# EIS_CO2_Power.net
KiCad netlist of a schematic drawn in Altium Designer
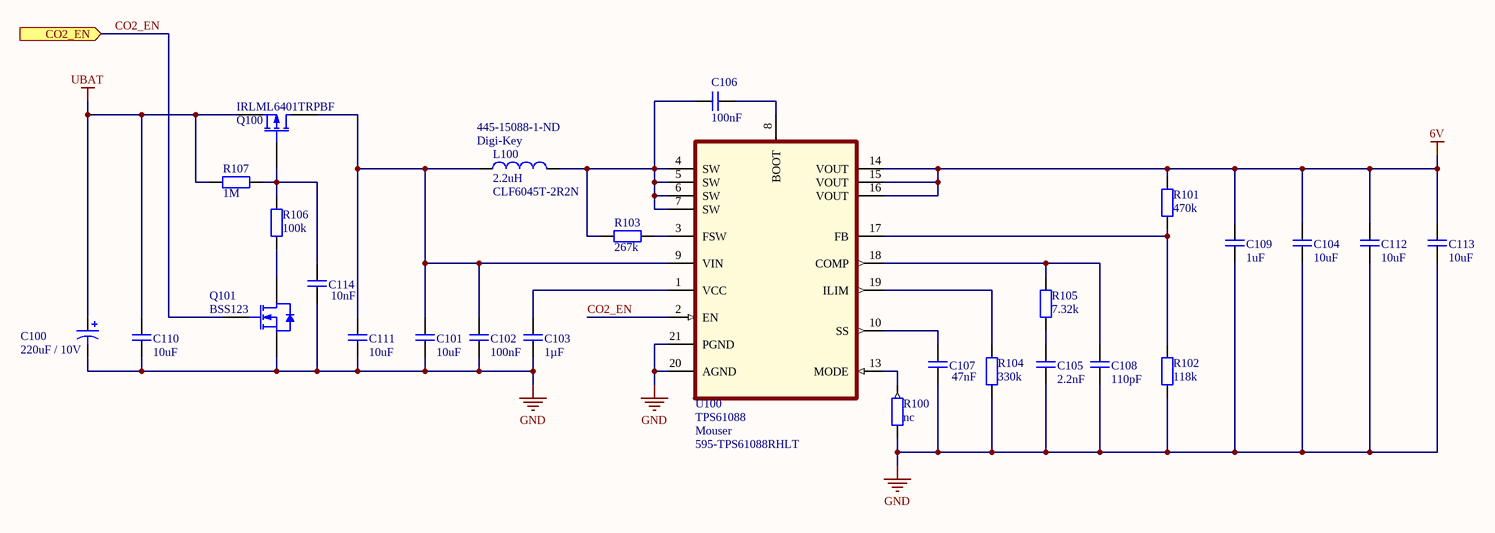
[diagram p0: EIS_CO2_Power.SchDoc]

(export (version "E")
  (design (tool "Eeschema 10.0.6"))
  (components
    (comp (ref "C100")
      (value "220uF / 10V")
      (footprint "D")
      (description "Polarized Capacitor (Surface Mount)")
      (fields (field (name "PUBLISHER") "Altium Limited"))
      (libsource (lib "Miscellaneous Devices") (part "Cap Pol3"))
    )
    (comp (ref "C101")
      (value "10uF")
      (footprint "CAPC3216N")
      (libsource (lib "My_Schlib_6_18") (part "Kondensator SMD Keramik"))
    )
    (comp (ref "C102")
      (value "100nF")
      (footprint "CAPC1608N")
      (libsource (lib "My_Schlib_6_18") (part "Kondensator SMD Keramik"))
    )
    (comp (ref "C103")
      (value "1µF")
      (footprint "CAPC1608N")
      (libsource (lib "My_Schlib_6_18") (part "Kondensator SMD Keramik"))
    )
    (comp (ref "C104")
      (value "10uF")
      (footprint "CAPC3216N")
      (libsource (lib "My_Schlib_6_18") (part "Kondensator SMD Keramik"))
    )
    (comp (ref "C105")
      (value "2.2nF")
      (footprint "CAPC1608N")
      (libsource (lib "My_Schlib_6_18") (part "Kondensator SMD Keramik"))
    )
    (comp (ref "C106")
      (value "100nF")
      (footprint "CAPC1608N")
      (libsource (lib "My_Schlib_6_18") (part "Kondensator SMD Keramik"))
    )
    (comp (ref "C107")
      (value "47nF")
      (footprint "CAPC1608N")
      (libsource (lib "My_Schlib_6_18") (part "Kondensator SMD Keramik"))
    )
    (comp (ref "C108")
      (value "110pF")
      (footprint "CAPC1608N")
      (libsource (lib "My_Schlib_6_18") (part "Kondensator SMD Keramik"))
    )
    (comp (ref "C109")
      (value "1uF")
      (footprint "CAPC3216N")
      (libsource (lib "My_Schlib_6_18") (part "Kondensator SMD Keramik"))
    )
    (comp (ref "C110")
      (value "10uF")
      (footprint "CAPC3216N")
      (libsource (lib "My_Schlib_6_18") (part "Kondensator SMD Keramik"))
    )
    (comp (ref "C111")
      (value "10uF")
      (footprint "CAPC3216N")
      (libsource (lib "My_Schlib_6_18") (part "Kondensator SMD Keramik"))
    )
    (comp (ref "C112")
      (value "10uF")
      (footprint "CAPC3216N")
      (libsource (lib "My_Schlib_6_18") (part "Kondensator SMD Keramik"))
    )
    (comp (ref "C113")
      (value "10uF")
      (footprint "CAPC3216N")
      (libsource (lib "My_Schlib_6_18") (part "Kondensator SMD Keramik"))
    )
    (comp (ref "C114")
      (value "10nF")
      (footprint "CAPC1608N")
      (libsource (lib "My_Schlib_6_18") (part "Kondensator SMD Keramik"))
    )
    (comp (ref "L100")
      (value "2.2uH")
      (footprint "CLF6045")
      (description "Inductor")
      (fields
        (field (name "SUPPLIER PART NUMBER 1") "CLF6045T-2R2N")
        (field (name "SUPPLIER 2") "Digi-Key")
        (field (name "SUPPLIER PART NUMBER 2") "445-15088-1-ND")
        (field (name "Comment") "CLF6045T-2R2N")
        (field (name "PUBLISHER") "Altium Limited")
      )
      (libsource (lib "MetaSensClampOn_BT") (part "Inductor"))
    )
    (comp (ref "Q100")
      (value "IRLML6401TRPBF")
      (footprint "SOT23_N")
      (description "P-Channel MOSFET")
      (fields (field (name "PUBLISHER") "Altium Limited"))
      (libsource (lib "Eis_Lib") (part "IRLML6401TRPBF"))
    )
    (comp (ref "Q101")
      (value "BSS123")
      (footprint "SOT23_N - BSS123")
      (description "N-channel Enhancement Mode Vertical D-MOSFET")
      (fields (field (name "PUBLISHER") "Altium Limited"))
      (libsource (lib "Philips Discrete MOSFET - Low Power") (part "BSS123"))
    )
    (comp (ref "R100")
      (value "nc")
      (footprint "RESC1608N")
      (description "RESC1608 (R0603)")
      (fields (field (name "PUBLISHER") "HSG Jürgen Merz"))
      (libsource (lib "MetaSensClampOn_BT") (part "RESC1608 (R0603)"))
    )
    (comp (ref "R101")
      (value "470k")
      (footprint "RESC1608N")
      (description "RESC1608 (R0603)")
      (fields (field (name "PUBLISHER") "HSG Jürgen Merz"))
      (libsource (lib "MetaSensClampOn_BT") (part "RESC1608 (R0603)"))
    )
    (comp (ref "R102")
      (value "118k")
      (footprint "RESC1608N")
      (description "RESC1608 (R0603)")
      (fields (field (name "PUBLISHER") "HSG Jürgen Merz"))
      (libsource (lib "MetaSensClampOn_BT") (part "RESC1608 (R0603)"))
    )
    (comp (ref "R103")
      (value "267k")
      (footprint "RESC1608N")
      (description "RESC1608 (R0603)")
      (fields (field (name "PUBLISHER") "HSG Jürgen Merz"))
      (libsource (lib "") (part "RESC1608 (R0603)_2"))
    )
    (comp (ref "R104")
      (value "330k")
      (footprint "RESC1608N")
      (description "RESC1608 (R0603)")
      (fields (field (name "PUBLISHER") "HSG Jürgen Merz"))
      (libsource (lib "MetaSensClampOn_BT") (part "RESC1608 (R0603)"))
    )
    (comp (ref "R105")
      (value "7.32k")
      (footprint "RESC1608N")
      (description "RESC1608 (R0603)")
      (fields (field (name "PUBLISHER") "HSG Jürgen Merz"))
      (libsource (lib "MetaSensClampOn_BT") (part "RESC1608 (R0603)"))
    )
    (comp (ref "R106")
      (value "100k")
      (footprint "RESC1608N")
      (description "RESC1608 (R0603)")
      (fields (field (name "PUBLISHER") "HSG Jürgen Merz"))
      (libsource (lib "") (part "RESC1608 (R0603)_1"))
    )
    (comp (ref "R107")
      (value "1M")
      (footprint "RESC1608N")
      (description "RESC1608 (R0603)")
      (fields (field (name "PUBLISHER") "HSG Jürgen Merz"))
      (libsource (lib "") (part "RESC1608 (R0603)_3"))
    )
    (comp (ref "U100")
      (value "TPS61088")
      (footprint "RHL0020A")
      (description "Boost Schaltregler, 2,7V - 12 Uin / 4.5V-12.6V Uout / 3A / 1µA Shutdown")
      (fields (field (name "SUPPLIER 1") "Mouser") (field (name "SUPPLIER PART NUMBER 1") "595-TPS61088RHLT"))
      (libsource (lib "Eis_Lib") (part "TPS61088"))
    )
  )
  (nets
    (net (code "1") (name "/CO2_EN") (class "Default")
      (node (ref "Q101") (pin "1") (pinfunction "G_1") (pintype "passive"))
      (node (ref "U100") (pin "2") (pinfunction "EN_2") (pintype "input"))
    )
    (net (code "2") (name "6V") (class "Default")
      (node (ref "C104") (pin "1") (pinfunction "1_1") (pintype "passive"))
      (node (ref "C109") (pin "1") (pinfunction "1_1") (pintype "passive"))
      (node (ref "C112") (pin "1") (pinfunction "1_1") (pintype "passive"))
      (node (ref "C113") (pin "1") (pinfunction "1_1") (pintype "passive"))
      (node (ref "R101") (pin "1") (pinfunction "1_1") (pintype "passive"))
      (node (ref "U100") (pin "14") (pinfunction "VOUT_14") (pintype "power_in"))
      (node (ref "U100") (pin "15") (pinfunction "VOUT_15") (pintype "power_in"))
      (node (ref "U100") (pin "16") (pinfunction "VOUT_16") (pintype "power_in"))
    )
    (net (code "3") (name "GND") (class "Default")
      (node (ref "C100") (pin "2") (pinfunction "2_2") (pintype "passive"))
      (node (ref "C101") (pin "2") (pinfunction "2_2") (pintype "passive"))
      (node (ref "C102") (pin "1") (pinfunction "1_1") (pintype "passive"))
      (node (ref "C103") (pin "1") (pinfunction "1_1") (pintype "passive"))
      (node (ref "C104") (pin "2") (pinfunction "2_2") (pintype "passive"))
      (node (ref "C105") (pin "1") (pinfunction "1_1") (pintype "passive"))
      (node (ref "C107") (pin "1") (pinfunction "1_1") (pintype "passive"))
      (node (ref "C108") (pin "1") (pinfunction "1_1") (pintype "passive"))
      (node (ref "C109") (pin "2") (pinfunction "2_2") (pintype "passive"))
      (node (ref "C110") (pin "2") (pinfunction "2_2") (pintype "passive"))
      (node (ref "C111") (pin "2") (pinfunction "2_2") (pintype "passive"))
      (node (ref "C112") (pin "2") (pinfunction "2_2") (pintype "passive"))
      (node (ref "C113") (pin "2") (pinfunction "2_2") (pintype "passive"))
      (node (ref "C114") (pin "1") (pinfunction "1_1") (pintype "passive"))
      (node (ref "Q101") (pin "2") (pinfunction "S_2") (pintype "passive"))
      (node (ref "R100") (pin "2") (pinfunction "2_2") (pintype "passive"))
      (node (ref "R102") (pin "2") (pinfunction "2_2") (pintype "passive"))
      (node (ref "R104") (pin "2") (pinfunction "2_2") (pintype "passive"))
      (node (ref "U100") (pin "20") (pinfunction "AGND_20") (pintype "power_in"))
      (node (ref "U100") (pin "21") (pinfunction "PGND_21") (pintype "power_in"))
    )
    (net (code "4") (name "Net-(C105-Pad2)") (class "Default")
      (node (ref "C105") (pin "2") (pinfunction "2_2") (pintype "passive"))
      (node (ref "R105") (pin "2") (pinfunction "2_2") (pintype "passive"))
    )
    (net (code "5") (name "Net-(C106-Pad1)") (class "Default")
      (node (ref "C106") (pin "1") (pinfunction "1_1") (pintype "passive"))
      (node (ref "L100") (pin "2") (pinfunction "2_2") (pintype "passive"))
      (node (ref "R103") (pin "2") (pinfunction "2_2") (pintype "passive"))
      (node (ref "U100") (pin "4") (pinfunction "SW_4") (pintype "passive"))
      (node (ref "U100") (pin "5") (pinfunction "SW_5") (pintype "passive"))
      (node (ref "U100") (pin "6") (pinfunction "SW_6") (pintype "passive"))
      (node (ref "U100") (pin "7") (pinfunction "SW_7") (pintype "passive"))
    )
    (net (code "6") (name "Net-(Q100-D)") (class "Default")
      (node (ref "C101") (pin "1") (pinfunction "1_1") (pintype "passive"))
      (node (ref "C102") (pin "2") (pinfunction "2_2") (pintype "passive"))
      (node (ref "C111") (pin "1") (pinfunction "1_1") (pintype "passive"))
      (node (ref "L100") (pin "1") (pinfunction "1_1") (pintype "passive"))
      (node (ref "Q100") (pin "3") (pinfunction "D_3") (pintype "passive"))
      (node (ref "U100") (pin "9") (pinfunction "VIN_9") (pintype "power_in"))
    )
    (net (code "7") (name "Net-(Q100-G)") (class "Default")
      (node (ref "C114") (pin "2") (pinfunction "2_2") (pintype "passive"))
      (node (ref "Q100") (pin "1") (pinfunction "G_1") (pintype "passive"))
      (node (ref "R106") (pin "2") (pinfunction "2_2") (pintype "passive"))
      (node (ref "R107") (pin "2") (pinfunction "2_2") (pintype "passive"))
    )
    (net (code "8") (name "Net-(Q101-D)") (class "Default")
      (node (ref "Q101") (pin "3") (pinfunction "D_3") (pintype "passive"))
      (node (ref "R106") (pin "1") (pinfunction "1_1") (pintype "passive"))
    )
    (net (code "9") (name "Net-(U100-BOOT)") (class "Default")
      (node (ref "C106") (pin "2") (pinfunction "2_2") (pintype "passive"))
      (node (ref "U100") (pin "8") (pinfunction "BOOT_8") (pintype "passive"))
    )
    (net (code "10") (name "Net-(U100-COMP)") (class "Default")
      (node (ref "C108") (pin "2") (pinfunction "2_2") (pintype "passive"))
      (node (ref "R105") (pin "1") (pinfunction "1_1") (pintype "passive"))
      (node (ref "U100") (pin "18") (pinfunction "COMP_18") (pintype "output"))
    )
    (net (code "11") (name "Net-(U100-FB)") (class "Default")
      (node (ref "R101") (pin "2") (pinfunction "2_2") (pintype "passive"))
      (node (ref "R102") (pin "1") (pinfunction "1_1") (pintype "passive"))
      (node (ref "U100") (pin "17") (pinfunction "FB_17") (pintype "passive"))
    )
    (net (code "12") (name "Net-(U100-FSW)") (class "Default")
      (node (ref "R103") (pin "1") (pinfunction "1_1") (pintype "passive"))
      (node (ref "U100") (pin "3") (pinfunction "FSW_3") (pintype "passive"))
    )
    (net (code "13") (name "Net-(U100-ILIM)") (class "Default")
      (node (ref "R104") (pin "1") (pinfunction "1_1") (pintype "passive"))
      (node (ref "U100") (pin "19") (pinfunction "ILIM_19") (pintype "output"))
    )
    (net (code "14") (name "Net-(U100-MODE)") (class "Default")
      (node (ref "R100") (pin "1") (pinfunction "1_1") (pintype "passive"))
      (node (ref "U100") (pin "13") (pinfunction "MODE_13") (pintype "input"))
    )
    (net (code "15") (name "Net-(U100-SS)") (class "Default")
      (node (ref "C107") (pin "2") (pinfunction "2_2") (pintype "passive"))
      (node (ref "U100") (pin "10") (pinfunction "SS_10") (pintype "output"))
    )
    (net (code "16") (name "Net-(U100-VCC)") (class "Default")
      (node (ref "C103") (pin "2") (pinfunction "2_2") (pintype "passive"))
      (node (ref "U100") (pin "1") (pinfunction "VCC_1") (pintype "passive"))
    )
    (net (code "17") (name "UBAT") (class "Default")
      (node (ref "C100") (pin "1") (pinfunction "1_1") (pintype "passive"))
      (node (ref "C110") (pin "1") (pinfunction "1_1") (pintype "passive"))
      (node (ref "Q100") (pin "2") (pinfunction "S_2") (pintype "passive"))
      (node (ref "R107") (pin "1") (pinfunction "1_1") (pintype "passive"))
    )
  )
)
